# antennaArray.net
KiCad netlist of a schematic drawn in Altium Designer
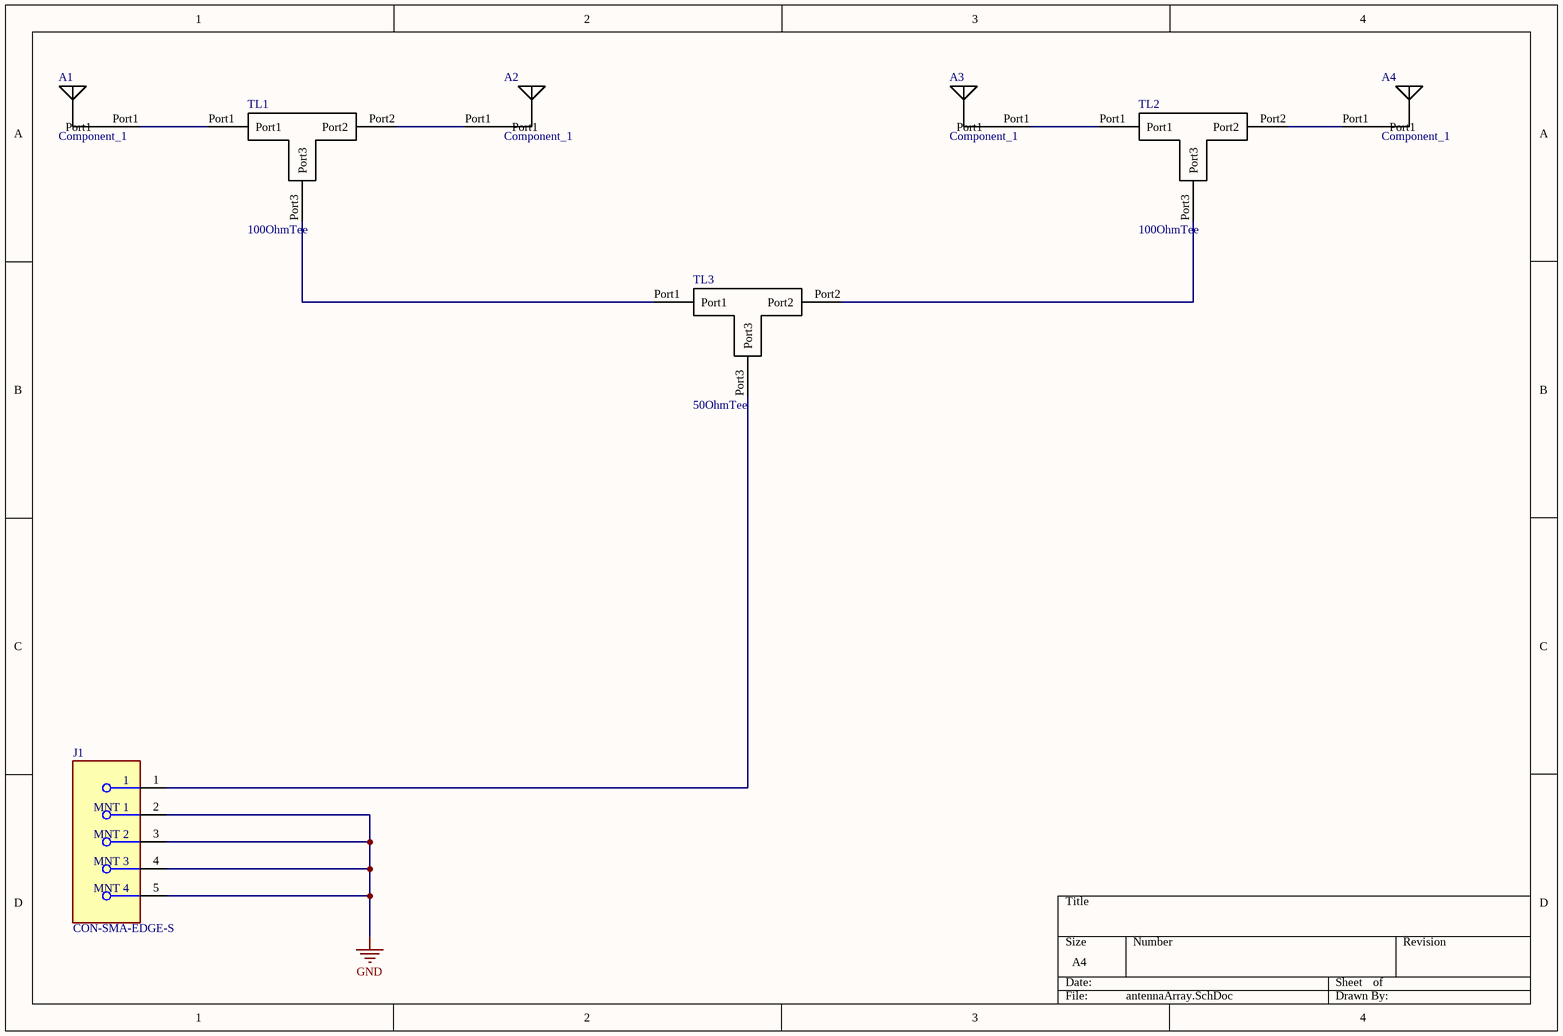
[diagram p0: antennaArray.SchDoc]

(export (version "E")
  (design (tool "Eeschema 10.0.6"))
  (components
    (comp (ref "A1")
      (value "Component_1")
      (footprint "5GHzPatch")
      (libsource (lib "patchAntennaArray") (part "Component_1"))
    )
    (comp (ref "A2")
      (value "Component_1")
      (footprint "5GHzPatch")
      (libsource (lib "patchAntennaArray") (part "Component_1"))
    )
    (comp (ref "A3")
      (value "Component_1")
      (footprint "5GHzPatch")
      (libsource (lib "patchAntennaArray") (part "Component_1"))
    )
    (comp (ref "A4")
      (value "Component_1")
      (footprint "5GHzPatch")
      (libsource (lib "patchAntennaArray") (part "Component_1"))
    )
    (comp (ref "J1")
      (value "CON-SMA-EDGE-S")
      (footprint "FP-CON-SMA-EDGE-S-MFG")
      (description "CONN SMA JACK STR EDGE MNT")
      (fields
        (field (name "OCTOPART") "https://octopart.com/con-sma-edge-s-rf+solutions-70967450")
        (field (name "MANUFACTURER") "RF Solutions Ltd.")
      )
      (libsource (lib "Altium Content Vault") (part "a163d97a771fcdd2fd1f1a9264c171f"))
    )
    (comp (ref "TL1")
      (value "100OhmTee")
      (footprint "100OhmTee")
      (libsource (lib "patchAntennaArray") (part "100OhmTee"))
    )
    (comp (ref "TL2")
      (value "100OhmTee")
      (footprint "100OhmTee")
      (libsource (lib "patchAntennaArray") (part "100OhmTee"))
    )
    (comp (ref "TL3")
      (value "50OhmTee")
      (footprint "50OhmTee")
      (libsource (lib "patchAntennaArray") (part "50OhmTee"))
    )
  )
  (nets
    (net (code "1") (name "GND") (class "Default")
      (node (ref "J1") (pin "2") (pinfunction "MNT_1_2") (pintype "passive"))
      (node (ref "J1") (pin "3") (pinfunction "MNT_2_3") (pintype "passive"))
      (node (ref "J1") (pin "4") (pinfunction "MNT_3_4") (pintype "passive"))
      (node (ref "J1") (pin "5") (pinfunction "MNT_4_5") (pintype "passive"))
    )
    (net (code "2") (name "Net-(A1-PadPort1)") (class "Default")
      (node (ref "A1") (pin "Port1") (pinfunction "Port1_Port1") (pintype "passive"))
      (node (ref "TL1") (pin "Port1") (pinfunction "Port1_Port1") (pintype "passive"))
    )
    (net (code "3") (name "Net-(A2-PadPort1)") (class "Default")
      (node (ref "A2") (pin "Port1") (pinfunction "Port1_Port1") (pintype "passive"))
      (node (ref "TL1") (pin "Port2") (pinfunction "Port2_Port2") (pintype "passive"))
    )
    (net (code "4") (name "Net-(A3-PadPort1)") (class "Default")
      (node (ref "A3") (pin "Port1") (pinfunction "Port1_Port1") (pintype "passive"))
      (node (ref "TL2") (pin "Port1") (pinfunction "Port1_Port1") (pintype "passive"))
    )
    (net (code "5") (name "Net-(A4-PadPort1)") (class "Default")
      (node (ref "A4") (pin "Port1") (pinfunction "Port1_Port1") (pintype "passive"))
      (node (ref "TL2") (pin "Port2") (pinfunction "Port2_Port2") (pintype "passive"))
    )
    (net (code "6") (name "Net-(J1-Pad1)") (class "Default")
      (node (ref "J1") (pin "1") (pinfunction "1_1") (pintype "passive"))
      (node (ref "TL3") (pin "Port3") (pinfunction "Port3_Port3") (pintype "passive"))
    )
    (net (code "7") (name "Net-(TL1-PadPort3)") (class "Default")
      (node (ref "TL1") (pin "Port3") (pinfunction "Port3_Port3") (pintype "passive"))
      (node (ref "TL3") (pin "Port1") (pinfunction "Port1_Port1") (pintype "passive"))
    )
    (net (code "8") (name "Net-(TL2-PadPort3)") (class "Default")
      (node (ref "TL2") (pin "Port3") (pinfunction "Port3_Port3") (pintype "passive"))
      (node (ref "TL3") (pin "Port2") (pinfunction "Port2_Port2") (pintype "passive"))
    )
  )
)
